# vca_chorus_pots.net
KiCad netlist of a schematic drawn in EAGLE
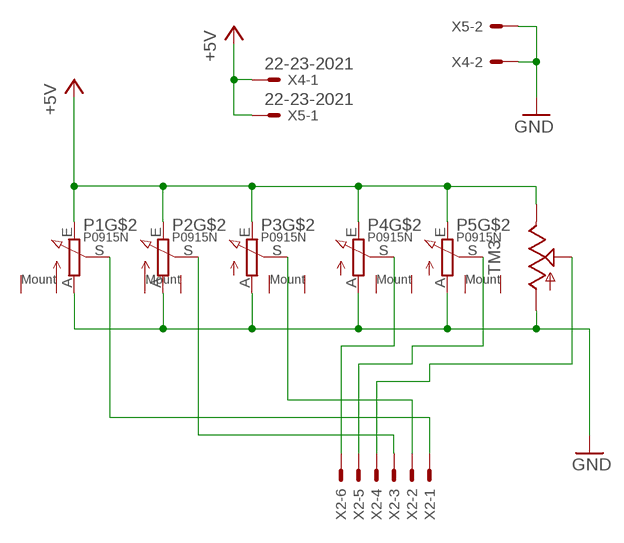
[diagram p0: schematic, sheet 1]

(export (version "E")
  (design (tool "Eeschema 10.0.6"))
  (components
    (comp (ref "P1")
      (value "P0915N")
      (footprint "eagle-import:P0915N")
      (libsource (lib "eagle-import") (part "P0915N"))
    )
    (comp (ref "P2")
      (value "P0915N")
      (footprint "eagle-import:P0915N")
      (libsource (lib "eagle-import") (part "P0915N"))
    )
    (comp (ref "P3")
      (value "P0915N")
      (footprint "eagle-import:P0915N")
      (libsource (lib "eagle-import") (part "P0915N"))
    )
    (comp (ref "P4")
      (value "P0915N")
      (footprint "eagle-import:P0915N")
      (libsource (lib "eagle-import") (part "P0915N"))
    )
    (comp (ref "P5")
      (value "P0915N")
      (footprint "eagle-import:P0915N")
      (libsource (lib "eagle-import") (part "P0915N"))
    )
    (comp (ref "TM3")
      (value "TRIMSLIDE60")
      (footprint "eagle-import:SLIDEPOT-60")
      (libsource (lib "eagle-import") (part "TRIMSLIDE60"))
    )
    (comp (ref "X2")
      (value "22-23-2061")
      (footprint "eagle-import:22-23-2061")
      (fields (field (name "MF") "MOLEX"))
      (libsource (lib "eagle-import") (part "22-23-2061"))
    )
    (comp (ref "X4")
      (value "22-23-2021")
      (footprint "eagle-import:22-23-2021")
      (fields (field (name "MF") "MOLEX"))
      (libsource (lib "eagle-import") (part "22-23-2021"))
    )
    (comp (ref "X5")
      (value "22-23-2021")
      (footprint "eagle-import:22-23-2021")
      (fields (field (name "MF") "MOLEX"))
      (libsource (lib "eagle-import") (part "22-23-2021"))
    )
  )
  (nets
    (net (code "1") (name "+5V") (class "Default")
      (node (ref "P1") (pin "E") (pinfunction "E_E") (pintype "passive"))
      (node (ref "P2") (pin "E") (pinfunction "E_E") (pintype "passive"))
      (node (ref "P3") (pin "E") (pinfunction "E_E") (pintype "passive"))
      (node (ref "P4") (pin "E") (pinfunction "E_E") (pintype "passive"))
      (node (ref "P5") (pin "E") (pinfunction "E_E") (pintype "passive"))
      (node (ref "TM3") (pin "B") (pinfunction "B_B") (pintype "passive"))
      (node (ref "X4") (pin "1") (pinfunction "S_1") (pintype "passive"))
      (node (ref "X5") (pin "1") (pinfunction "S_1") (pintype "passive"))
    )
    (net (code "2") (name "GND") (class "Default")
      (node (ref "P1") (pin "A") (pinfunction "A_A") (pintype "passive"))
      (node (ref "P2") (pin "A") (pinfunction "A_A") (pintype "passive"))
      (node (ref "P3") (pin "A") (pinfunction "A_A") (pintype "passive"))
      (node (ref "P4") (pin "A") (pinfunction "A_A") (pintype "passive"))
      (node (ref "P5") (pin "A") (pinfunction "A_A") (pintype "passive"))
      (node (ref "TM3") (pin "A") (pinfunction "A_A") (pintype "passive"))
      (node (ref "X4") (pin "2") (pinfunction "S_2") (pintype "passive"))
      (node (ref "X5") (pin "2") (pinfunction "S_2") (pintype "passive"))
    )
    (net (code "3") (name "Net-(X2A-S)") (class "Default")
      (node (ref "P1") (pin "S") (pinfunction "S_S") (pintype "passive"))
      (node (ref "X2") (pin "1") (pinfunction "S_1") (pintype "passive"))
    )
    (net (code "4") (name "Net-(X2B-S)") (class "Default")
      (node (ref "P3") (pin "S") (pinfunction "S_S") (pintype "passive"))
      (node (ref "X2") (pin "2") (pinfunction "S_2") (pintype "passive"))
    )
    (net (code "5") (name "Net-(X2C-S)") (class "Default")
      (node (ref "P2") (pin "S") (pinfunction "S_S") (pintype "passive"))
      (node (ref "X2") (pin "3") (pinfunction "S_3") (pintype "passive"))
    )
    (net (code "6") (name "Net-(X2D-S)") (class "Default")
      (node (ref "TM3") (pin "WIPER") (pinfunction "WIPER_WIPER") (pintype "passive"))
      (node (ref "X2") (pin "4") (pinfunction "S_4") (pintype "passive"))
    )
    (net (code "7") (name "Net-(X2E-S)") (class "Default")
      (node (ref "P5") (pin "S") (pinfunction "S_S") (pintype "passive"))
      (node (ref "X2") (pin "5") (pinfunction "S_5") (pintype "passive"))
    )
    (net (code "8") (name "Net-(X2F-S)") (class "Default")
      (node (ref "P4") (pin "S") (pinfunction "S_S") (pintype "passive"))
      (node (ref "X2") (pin "6") (pinfunction "S_6") (pintype "passive"))
    )
    (net (code "9") (name "unconnected-(P1A-GND-PadGND@1)") (class "Default")
      (node (ref "P1") (pin "GND@1") (pinfunction "GND_GND@1") (pintype "passive"))
    )
    (net (code "10") (name "unconnected-(P1A-GND-PadGND@2)") (class "Default")
      (node (ref "P1") (pin "GND@2") (pinfunction "GND_GND@2") (pintype "passive"))
    )
    (net (code "11") (name "unconnected-(P2A-GND-PadGND@1)") (class "Default")
      (node (ref "P2") (pin "GND@1") (pinfunction "GND_GND@1") (pintype "passive"))
    )
    (net (code "12") (name "unconnected-(P2A-GND-PadGND@2)") (class "Default")
      (node (ref "P2") (pin "GND@2") (pinfunction "GND_GND@2") (pintype "passive"))
    )
    (net (code "13") (name "unconnected-(P3A-GND-PadGND@1)") (class "Default")
      (node (ref "P3") (pin "GND@1") (pinfunction "GND_GND@1") (pintype "passive"))
    )
    (net (code "14") (name "unconnected-(P3A-GND-PadGND@2)") (class "Default")
      (node (ref "P3") (pin "GND@2") (pinfunction "GND_GND@2") (pintype "passive"))
    )
    (net (code "15") (name "unconnected-(P4A-GND-PadGND@1)") (class "Default")
      (node (ref "P4") (pin "GND@1") (pinfunction "GND_GND@1") (pintype "passive"))
    )
    (net (code "16") (name "unconnected-(P4A-GND-PadGND@2)") (class "Default")
      (node (ref "P4") (pin "GND@2") (pinfunction "GND_GND@2") (pintype "passive"))
    )
    (net (code "17") (name "unconnected-(P5A-GND-PadGND@1)") (class "Default")
      (node (ref "P5") (pin "GND@1") (pinfunction "GND_GND@1") (pintype "passive"))
    )
    (net (code "18") (name "unconnected-(P5A-GND-PadGND@2)") (class "Default")
      (node (ref "P5") (pin "GND@2") (pinfunction "GND_GND@2") (pintype "passive"))
    )
  )
)
